# TSAL_logic.net
KiCad netlist of a schematic drawn in EAGLE
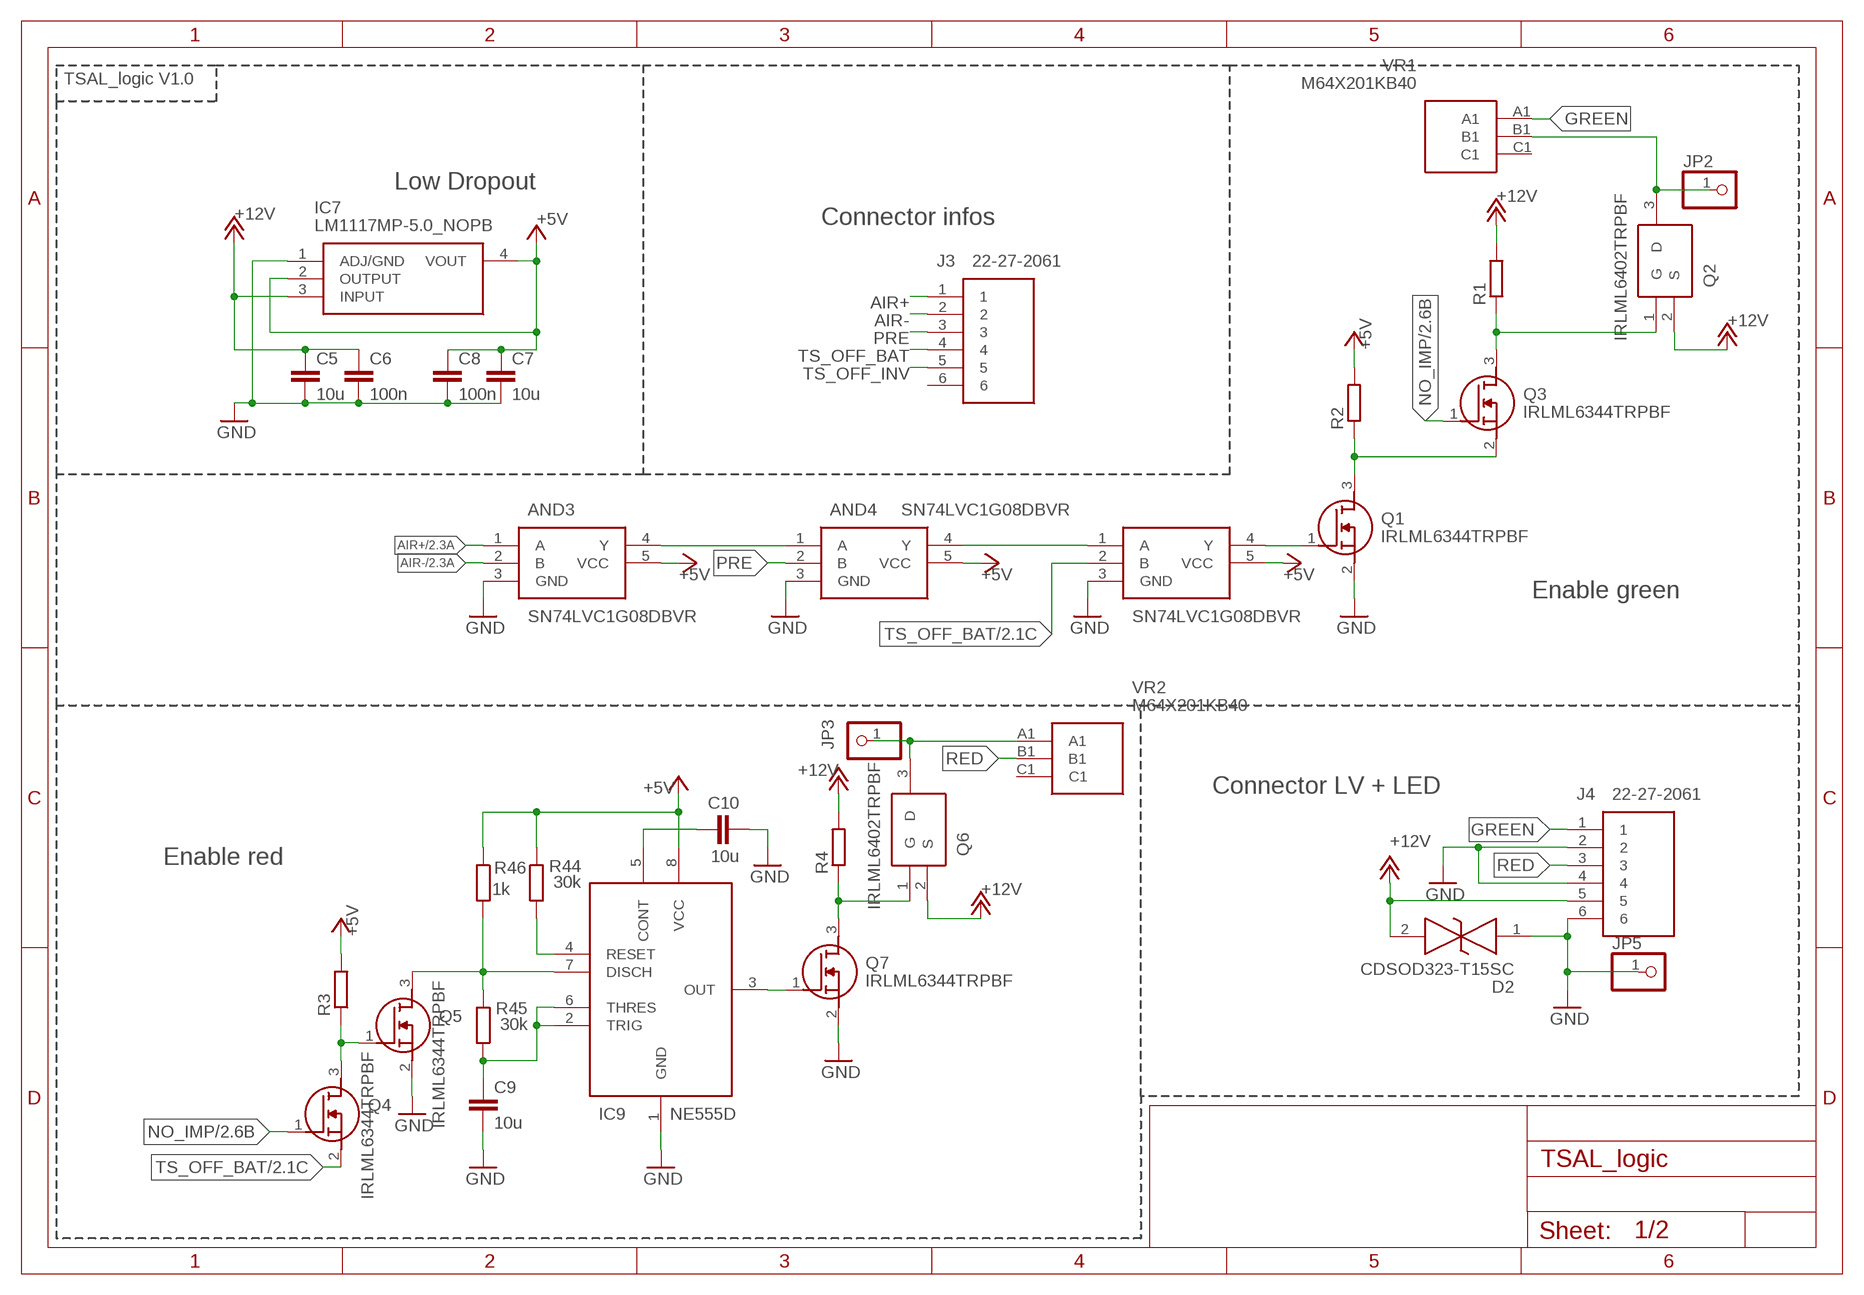
[diagram p0: schematic, sheet 1]
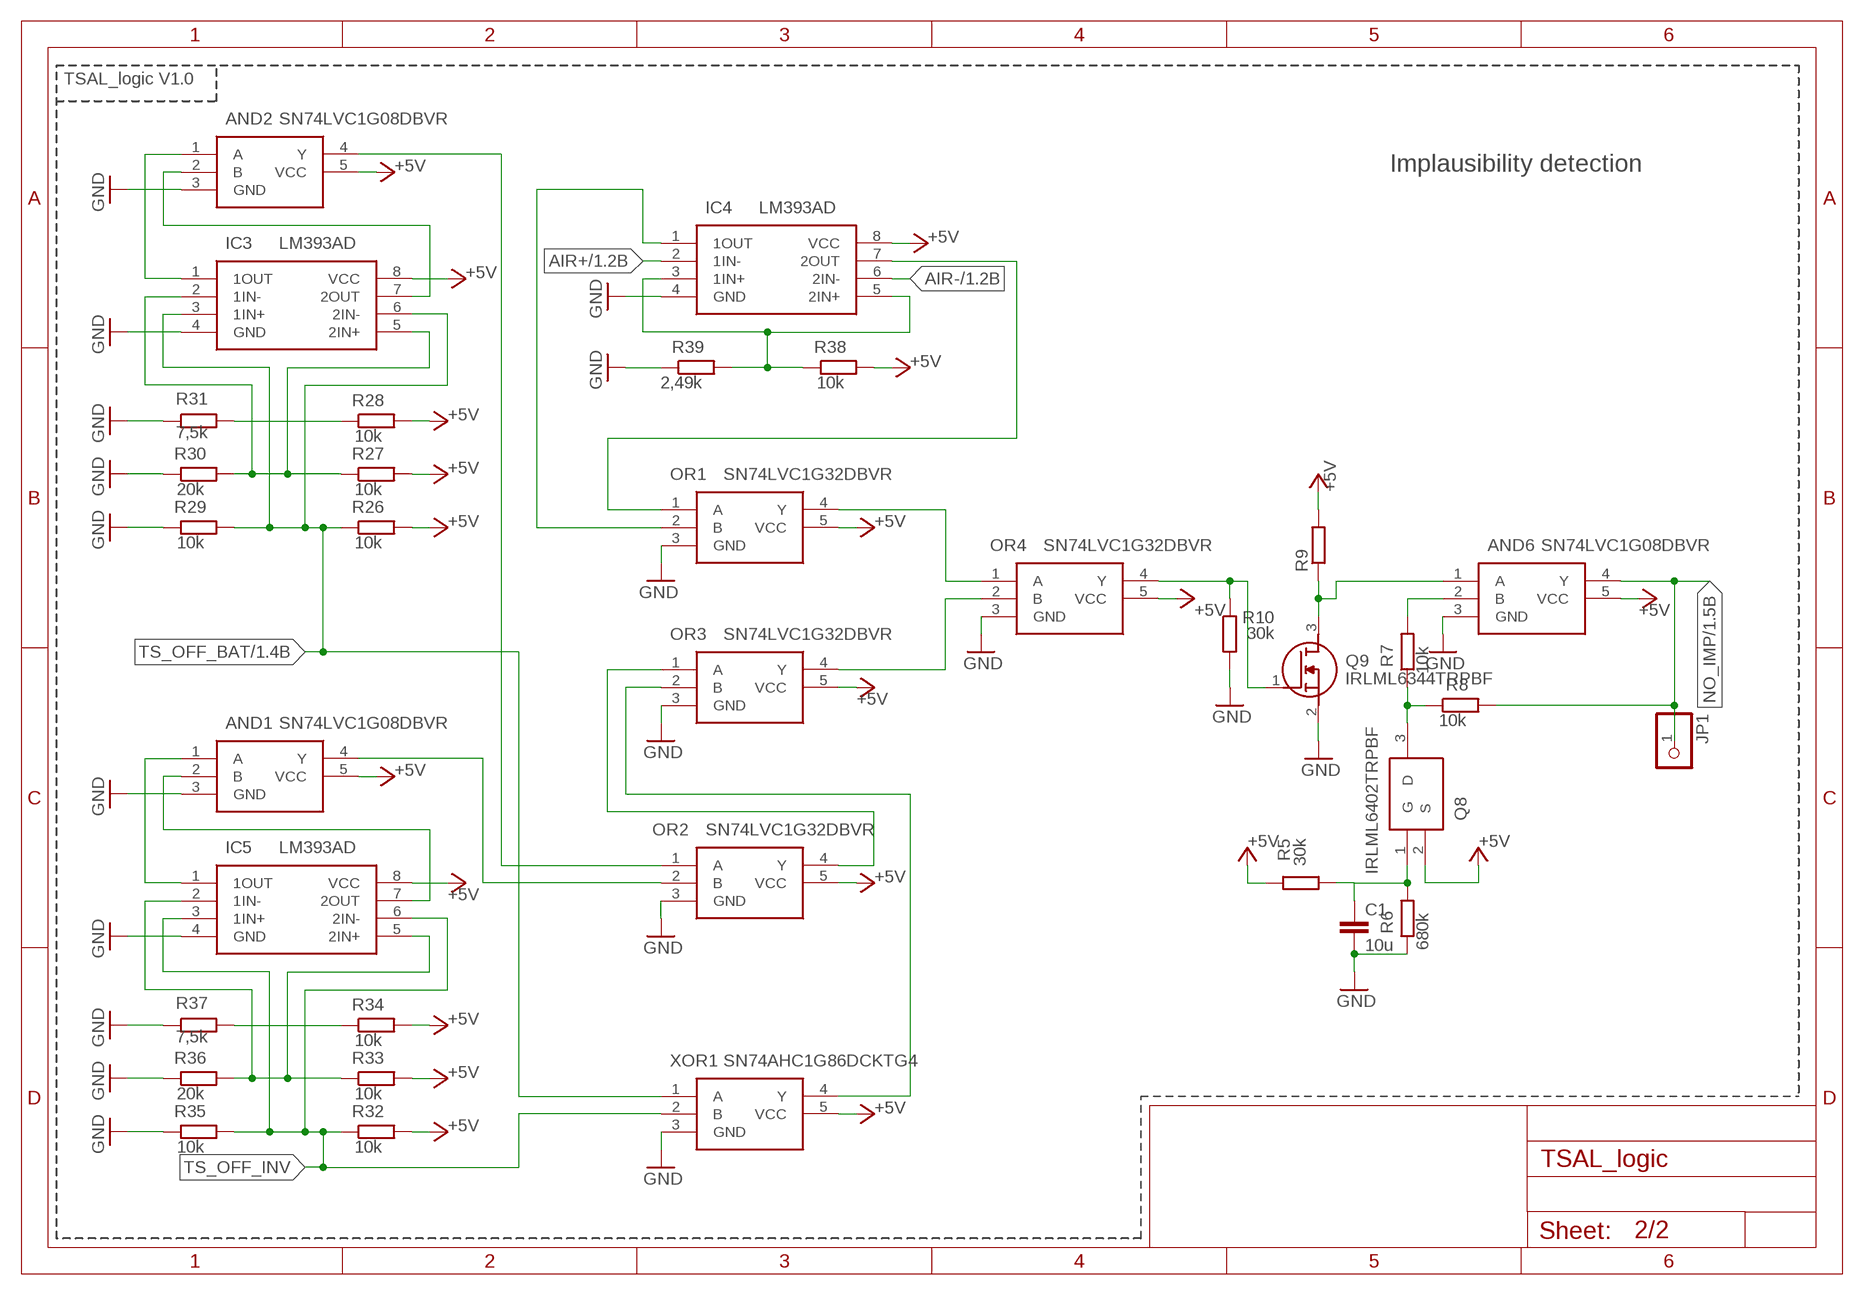
[diagram p1: schematic, sheet 2]

(export (version "E")
  (design (tool "Eeschema 10.0.6"))
  (components
    (comp (ref "AND1")
      (value "SN74LVC1G08DBVR")
      (footprint "eagle-import:SOT95P280X145-5N")
      (fields (field (name "MOUSER_PART_NUMBER") "595-SN74LVC1G08DBVR"))
      (libsource (lib "eagle-import") (part "SN74LVC1G08DBVR"))
    )
    (comp (ref "AND2")
      (value "SN74LVC1G08DBVR")
      (footprint "eagle-import:SOT95P280X145-5N")
      (fields (field (name "MOUSER_PART_NUMBER") "595-SN74LVC1G08DBVR"))
      (libsource (lib "eagle-import") (part "SN74LVC1G08DBVR"))
    )
    (comp (ref "AND6")
      (value "SN74LVC1G08DBVR")
      (footprint "eagle-import:SOT95P280X145-5N")
      (fields (field (name "MOUSER_PART_NUMBER") "595-SN74LVC1G08DBVR"))
      (libsource (lib "eagle-import") (part "SN74LVC1G08DBVR"))
    )
    (comp (ref "C1")
      (value "10u")
      (footprint "eagle-import:C1206")
      (libsource (lib "eagle-import") (part "C-EUC1206"))
    )
    (comp (ref "IC3")
      (value "LM393AD")
      (footprint "eagle-import:SOIC127P600X175-8N")
      (fields (field (name "RS_PART_NUMBER") "5171905P"))
      (libsource (lib "eagle-import") (part "LM393AD"))
    )
    (comp (ref "IC4")
      (value "LM393AD")
      (footprint "eagle-import:SOIC127P600X175-8N")
      (fields (field (name "RS_PART_NUMBER") "5171905P"))
      (libsource (lib "eagle-import") (part "LM393AD"))
    )
    (comp (ref "IC5")
      (value "LM393AD")
      (footprint "eagle-import:SOIC127P600X175-8N")
      (fields (field (name "RS_PART_NUMBER") "5171905P"))
      (libsource (lib "eagle-import") (part "LM393AD"))
    )
    (comp (ref "JP1")
      (value "PINHD-1X1")
      (footprint "eagle-import:1X01")
      (libsource (lib "eagle-import") (part "PINHD-1X1"))
    )
    (comp (ref "OR1")
      (value "SN74LVC1G32DBVR")
      (footprint "eagle-import:SOT95P280X145-5N")
      (fields (field (name "RS_PART_NUMBER") "0527669"))
      (libsource (lib "eagle-import") (part "SN74LVC1G32DBVR"))
    )
    (comp (ref "OR2")
      (value "SN74LVC1G32DBVR")
      (footprint "eagle-import:SOT95P280X145-5N")
      (fields (field (name "RS_PART_NUMBER") "0527669"))
      (libsource (lib "eagle-import") (part "SN74LVC1G32DBVR"))
    )
    (comp (ref "OR3")
      (value "SN74LVC1G32DBVR")
      (footprint "eagle-import:SOT95P280X145-5N")
      (fields (field (name "RS_PART_NUMBER") "0527669") (field (name "SPICEPREFIX") "X"))
      (libsource (lib "eagle-import") (part "SN74LVC1G32DBVR"))
    )
    (comp (ref "OR4")
      (value "SN74LVC1G32DBVR")
      (footprint "eagle-import:SOT95P280X145-5N")
      (fields (field (name "RS_PART_NUMBER") "0527669"))
      (libsource (lib "eagle-import") (part "SN74LVC1G32DBVR"))
    )
    (comp (ref "Q8")
      (value "IRLML6402TRPBF")
      (footprint "eagle-import:SOT95P237X112-3N")
      (fields (field (name "RS_PART_NUMBER") "0301322P"))
      (libsource (lib "eagle-import") (part "IRLML6402TRPBF"))
    )
    (comp (ref "Q9")
      (value "IRLML6344TRPBF")
      (footprint "eagle-import:SOT95P237X112-3N")
      (fields (field (name "RS_PART_NUMBER") "7377225P"))
      (libsource (lib "eagle-import") (part "IRLML6344TRPBF"))
    )
    (comp (ref "R5")
      (value "30k")
      (footprint "eagle-import:R1206")
      (libsource (lib "eagle-import") (part "R-EU_R1206"))
    )
    (comp (ref "R6")
      (value "680k")
      (footprint "eagle-import:R0603")
      (libsource (lib "eagle-import") (part "R-EU_R0603"))
    )
    (comp (ref "R7")
      (value "10k")
      (footprint "eagle-import:R0603")
      (libsource (lib "eagle-import") (part "R-EU_R0603"))
    )
    (comp (ref "R8")
      (value "10k")
      (footprint "eagle-import:R0603")
      (libsource (lib "eagle-import") (part "R-EU_R0603"))
    )
    (comp (ref "R9")
      (value "R-EU_R0603")
      (footprint "eagle-import:R0603")
      (libsource (lib "eagle-import") (part "R-EU_R0603"))
    )
    (comp (ref "R10")
      (value "30k")
      (footprint "eagle-import:R1206")
      (libsource (lib "eagle-import") (part "R-EU_R1206"))
    )
    (comp (ref "R26")
      (value "10k")
      (footprint "eagle-import:R0603")
      (libsource (lib "eagle-import") (part "R-EU_R0603"))
    )
    (comp (ref "R27")
      (value "10k")
      (footprint "eagle-import:R0603")
      (libsource (lib "eagle-import") (part "R-EU_R0603"))
    )
    (comp (ref "R28")
      (value "10k")
      (footprint "eagle-import:R0603")
      (libsource (lib "eagle-import") (part "R-EU_R0603"))
    )
    (comp (ref "R29")
      (value "10k")
      (footprint "eagle-import:R0603")
      (libsource (lib "eagle-import") (part "R-EU_R0603"))
    )
    (comp (ref "R30")
      (value "20k")
      (footprint "eagle-import:R0603")
      (libsource (lib "eagle-import") (part "R-EU_R0603"))
    )
    (comp (ref "R31")
      (value "7,5k")
      (footprint "eagle-import:R0805")
      (libsource (lib "eagle-import") (part "R-EU_R0805"))
    )
    (comp (ref "R32")
      (value "10k")
      (footprint "eagle-import:R0603")
      (libsource (lib "eagle-import") (part "R-EU_R0603"))
    )
    (comp (ref "R33")
      (value "10k")
      (footprint "eagle-import:R0603")
      (libsource (lib "eagle-import") (part "R-EU_R0603"))
    )
    (comp (ref "R34")
      (value "10k")
      (footprint "eagle-import:R0603")
      (libsource (lib "eagle-import") (part "R-EU_R0603"))
    )
    (comp (ref "R35")
      (value "10k")
      (footprint "eagle-import:R0603")
      (libsource (lib "eagle-import") (part "R-EU_R0603"))
    )
    (comp (ref "R36")
      (value "20k")
      (footprint "eagle-import:R0603")
      (libsource (lib "eagle-import") (part "R-EU_R0603"))
    )
    (comp (ref "R37")
      (value "7,5k")
      (footprint "eagle-import:R0805")
      (libsource (lib "eagle-import") (part "R-EU_R0805"))
    )
    (comp (ref "R38")
      (value "10k")
      (footprint "eagle-import:R0603")
      (libsource (lib "eagle-import") (part "R-EU_R0603"))
    )
    (comp (ref "R39")
      (value "2,49k")
      (footprint "eagle-import:R0603")
      (libsource (lib "eagle-import") (part "R-EU_R0603"))
    )
    (comp (ref "XOR1")
      (value "SN74AHC1G86DCKTG4")
      (footprint "eagle-import:SOT65P210X110-5N")
      (fields (field (name "MOUSER_PART_NUMBER") "595-74AHC1G86DCKTG4"))
      (libsource (lib "eagle-import") (part "SN74AHC1G86DCKTG4"))
    )
    (comp (ref "AND3")
      (value "SN74LVC1G08DBVR")
      (footprint "eagle-import:SOT95P280X145-5N")
      (fields (field (name "MOUSER_PART_NUMBER") "595-SN74LVC1G08DBVR"))
      (libsource (lib "eagle-import") (part "SN74LVC1G08DBVR"))
    )
    (comp (ref "AND4")
      (value "SN74LVC1G08DBVR")
      (footprint "eagle-import:SOT95P280X145-5N")
      (fields (field (name "MOUSER_PART_NUMBER") "595-SN74LVC1G08DBVR"))
      (libsource (lib "eagle-import") (part "SN74LVC1G08DBVR"))
    )
    (comp (ref "AND5")
      (value "SN74LVC1G08DBVR")
      (footprint "eagle-import:SOT95P280X145-5N")
      (fields (field (name "MOUSER_PART_NUMBER") "595-SN74LVC1G08DBVR"))
      (libsource (lib "eagle-import") (part "SN74LVC1G08DBVR"))
    )
    (comp (ref "C5")
      (value "10u")
      (footprint "eagle-import:C1206")
      (libsource (lib "eagle-import") (part "C-EUC1206"))
    )
    (comp (ref "C6")
      (value "100n")
      (footprint "eagle-import:C0603")
      (libsource (lib "eagle-import") (part "C-EUC0603"))
    )
    (comp (ref "C7")
      (value "10u")
      (footprint "eagle-import:C1206")
      (libsource (lib "eagle-import") (part "C-EUC1206"))
    )
    (comp (ref "C8")
      (value "100n")
      (footprint "eagle-import:C0603")
      (libsource (lib "eagle-import") (part "C-EUC0603"))
    )
    (comp (ref "C9")
      (value "10u")
      (footprint "eagle-import:C1206")
      (libsource (lib "eagle-import") (part "C-EUC1206"))
    )
    (comp (ref "C10")
      (value "10u")
      (footprint "eagle-import:C1206")
      (libsource (lib "eagle-import") (part "C-EUC1206"))
    )
    (comp (ref "D2")
      (value "CDSOD323-T15SC")
      (footprint "eagle-import:SOD-323")
      (fields (field (name "RS_PART_NUMBER") "7734570"))
      (libsource (lib "eagle-import") (part "CDSOD323-T15SC"))
    )
    (comp (ref "IC7")
      (value "LM1117MP-5.0_NOPB")
      (footprint "eagle-import:SOT230P700X180-4N")
      (fields
        (field (name "ARROW_PART_NUMBER") "LM1117MP-5.0/NOPB")
        (field (name "MOUSER_PART_NUMBER") "926-LM1117MP-5.0NOPB")
      )
      (libsource (lib "eagle-import") (part "LM1117MP-5.0_NOPB"))
    )
    (comp (ref "IC9")
      (value "NE555D")
      (footprint "eagle-import:SOIC127P600X175-8N")
      (fields (field (name "RS_PART_NUMBER") "6624661P"))
      (libsource (lib "eagle-import") (part "NE555D"))
    )
    (comp (ref "J3")
      (value "22-27-2061")
      (footprint "eagle-import:HDRV6W64P0X254_1X6_1524X580X11")
      (fields (field (name "RS_PART_NUMBER") "4838506P"))
      (libsource (lib "eagle-import") (part "22-27-2061"))
    )
    (comp (ref "J4")
      (value "22-27-2061")
      (footprint "eagle-import:HDRV6W64P0X254_1X6_1524X580X11")
      (fields (field (name "RS_PART_NUMBER") "4838506P"))
      (libsource (lib "eagle-import") (part "22-27-2061"))
    )
    (comp (ref "JP2")
      (value "PINHD-1X1")
      (footprint "eagle-import:1X01")
      (libsource (lib "eagle-import") (part "PINHD-1X1"))
    )
    (comp (ref "JP3")
      (value "PINHD-1X1")
      (footprint "eagle-import:1X01")
      (libsource (lib "eagle-import") (part "PINHD-1X1"))
    )
    (comp (ref "JP5")
      (value "PINHD-1X1")
      (footprint "eagle-import:1X01")
      (libsource (lib "eagle-import") (part "PINHD-1X1"))
    )
    (comp (ref "Q1")
      (value "IRLML6344TRPBF")
      (footprint "eagle-import:SOT95P237X112-3N")
      (fields (field (name "RS_PART_NUMBER") "7377225P"))
      (libsource (lib "eagle-import") (part "IRLML6344TRPBF"))
    )
    (comp (ref "Q2")
      (value "IRLML6402TRPBF")
      (footprint "eagle-import:SOT95P237X112-3N")
      (fields (field (name "RS_PART_NUMBER") "0301322P"))
      (libsource (lib "eagle-import") (part "IRLML6402TRPBF"))
    )
    (comp (ref "Q3")
      (value "IRLML6344TRPBF")
      (footprint "eagle-import:SOT95P237X112-3N")
      (fields (field (name "RS_PART_NUMBER") "7377225P"))
      (libsource (lib "eagle-import") (part "IRLML6344TRPBF"))
    )
    (comp (ref "Q4")
      (value "IRLML6344TRPBF")
      (footprint "eagle-import:SOT95P237X112-3N")
      (fields (field (name "RS_PART_NUMBER") "7377225P"))
      (libsource (lib "eagle-import") (part "IRLML6344TRPBF"))
    )
    (comp (ref "Q5")
      (value "IRLML6344TRPBF")
      (footprint "eagle-import:SOT95P237X112-3N")
      (fields (field (name "RS_PART_NUMBER") "7377225P"))
      (libsource (lib "eagle-import") (part "IRLML6344TRPBF"))
    )
    (comp (ref "Q6")
      (value "IRLML6402TRPBF")
      (footprint "eagle-import:SOT95P237X112-3N")
      (fields (field (name "RS_PART_NUMBER") "0301322P"))
      (libsource (lib "eagle-import") (part "IRLML6402TRPBF"))
    )
    (comp (ref "Q7")
      (value "IRLML6344TRPBF")
      (footprint "eagle-import:SOT95P237X112-3N")
      (fields (field (name "RS_PART_NUMBER") "7377225P"))
      (libsource (lib "eagle-import") (part "IRLML6344TRPBF"))
    )
    (comp (ref "R1")
      (value "R-EU_R0603")
      (footprint "eagle-import:R0603")
      (libsource (lib "eagle-import") (part "R-EU_R0603"))
    )
    (comp (ref "R2")
      (value "R-EU_R0603")
      (footprint "eagle-import:R0603")
      (libsource (lib "eagle-import") (part "R-EU_R0603"))
    )
    (comp (ref "R3")
      (value "R-EU_R0603")
      (footprint "eagle-import:R0603")
      (libsource (lib "eagle-import") (part "R-EU_R0603"))
    )
    (comp (ref "R4")
      (value "R-EU_R0603")
      (footprint "eagle-import:R0603")
      (libsource (lib "eagle-import") (part "R-EU_R0603"))
    )
    (comp (ref "R44")
      (value "30k")
      (footprint "eagle-import:R1206")
      (libsource (lib "eagle-import") (part "R-EU_R1206"))
    )
    (comp (ref "R45")
      (value "30k")
      (footprint "eagle-import:R1206")
      (libsource (lib "eagle-import") (part "R-EU_R1206"))
    )
    (comp (ref "R46")
      (value "1k")
      (footprint "eagle-import:R1206")
      (libsource (lib "eagle-import") (part "R-EU_R1206"))
    )
    (comp (ref "VR1")
      (value "M64X201KB40")
      (footprint "eagle-import:M64X201KB40")
      (fields (field (name "MOUSER_PART_NUMBER") "594-64X201"))
      (libsource (lib "eagle-import") (part "M64X201KB40"))
    )
    (comp (ref "VR2")
      (value "M64X201KB40")
      (footprint "eagle-import:M64X201KB40")
      (fields (field (name "MOUSER_PART_NUMBER") "594-64X201"))
      (libsource (lib "eagle-import") (part "M64X201KB40"))
    )
  )
  (nets
    (net (code "1") (name "+5V") (class "Default")
      (node (ref "AND1") (pin "5") (pinfunction "VCC_5") (pintype "power_in"))
      (node (ref "AND2") (pin "5") (pinfunction "VCC_5") (pintype "power_in"))
      (node (ref "AND3") (pin "5") (pinfunction "VCC_5") (pintype "power_in"))
      (node (ref "AND4") (pin "5") (pinfunction "VCC_5") (pintype "power_in"))
      (node (ref "AND5") (pin "5") (pinfunction "VCC_5") (pintype "power_in"))
      (node (ref "AND6") (pin "5") (pinfunction "VCC_5") (pintype "power_in"))
      (node (ref "C7") (pin "1") (pinfunction "1_1") (pintype "passive"))
      (node (ref "C8") (pin "1") (pinfunction "1_1") (pintype "passive"))
      (node (ref "IC3") (pin "8") (pinfunction "VCC_8") (pintype "bidirectional"))
      (node (ref "IC4") (pin "8") (pinfunction "VCC_8") (pintype "bidirectional"))
      (node (ref "IC5") (pin "8") (pinfunction "VCC_8") (pintype "bidirectional"))
      (node (ref "IC7") (pin "2") (pinfunction "OUTPUT_2") (pintype "bidirectional"))
      (node (ref "IC7") (pin "4") (pinfunction "VOUT_4") (pintype "bidirectional"))
      (node (ref "IC9") (pin "8") (pinfunction "VCC_8") (pintype "bidirectional"))
      (node (ref "OR1") (pin "5") (pinfunction "VCC_5") (pintype "bidirectional"))
      (node (ref "OR2") (pin "5") (pinfunction "VCC_5") (pintype "bidirectional"))
      (node (ref "OR3") (pin "5") (pinfunction "VCC_5") (pintype "bidirectional"))
      (node (ref "OR4") (pin "5") (pinfunction "VCC_5") (pintype "bidirectional"))
      (node (ref "Q8") (pin "2") (pinfunction "S_2") (pintype "bidirectional"))
      (node (ref "R2") (pin "2") (pinfunction "2_2") (pintype "passive"))
      (node (ref "R26") (pin "2") (pinfunction "2_2") (pintype "passive"))
      (node (ref "R27") (pin "2") (pinfunction "2_2") (pintype "passive"))
      (node (ref "R28") (pin "2") (pinfunction "2_2") (pintype "passive"))
      (node (ref "R3") (pin "2") (pinfunction "2_2") (pintype "passive"))
      (node (ref "R32") (pin "2") (pinfunction "2_2") (pintype "passive"))
      (node (ref "R33") (pin "2") (pinfunction "2_2") (pintype "passive"))
      (node (ref "R34") (pin "2") (pinfunction "2_2") (pintype "passive"))
      (node (ref "R38") (pin "2") (pinfunction "2_2") (pintype "passive"))
      (node (ref "R44") (pin "1") (pinfunction "1_1") (pintype "passive"))
      (node (ref "R46") (pin "1") (pinfunction "1_1") (pintype "passive"))
      (node (ref "R5") (pin "1") (pinfunction "1_1") (pintype "passive"))
      (node (ref "R9") (pin "2") (pinfunction "2_2") (pintype "passive"))
      (node (ref "XOR1") (pin "5") (pinfunction "VCC_5") (pintype "bidirectional"))
    )
    (net (code "2") (name "+12V") (class "Default")
      (node (ref "C5") (pin "1") (pinfunction "1_1") (pintype "passive"))
      (node (ref "C6") (pin "1") (pinfunction "1_1") (pintype "passive"))
      (node (ref "D2") (pin "2") (pinfunction "2_2") (pintype "bidirectional"))
      (node (ref "IC7") (pin "3") (pinfunction "INPUT_3") (pintype "bidirectional"))
      (node (ref "J4") (pin "5") (pinfunction "5_5") (pintype "bidirectional"))
      (node (ref "Q2") (pin "2") (pinfunction "S_2") (pintype "bidirectional"))
      (node (ref "Q6") (pin "2") (pinfunction "S_2") (pintype "bidirectional"))
      (node (ref "R1") (pin "2") (pinfunction "2_2") (pintype "passive"))
      (node (ref "R4") (pin "2") (pinfunction "2_2") (pintype "passive"))
    )
    (net (code "3") (name "AIR+") (class "Default")
      (node (ref "AND3") (pin "1") (pinfunction "A_1") (pintype "input"))
      (node (ref "IC4") (pin "2") (pinfunction "1IN-_2") (pintype "bidirectional"))
      (node (ref "J3") (pin "1") (pinfunction "1_1") (pintype "bidirectional"))
    )
    (net (code "4") (name "AIR-") (class "Default")
      (node (ref "AND3") (pin "2") (pinfunction "B_2") (pintype "input"))
      (node (ref "IC4") (pin "6") (pinfunction "2IN-_6") (pintype "bidirectional"))
      (node (ref "J3") (pin "2") (pinfunction "2_2") (pintype "bidirectional"))
    )
    (net (code "5") (name "GND") (class "Default")
      (node (ref "AND1") (pin "3") (pinfunction "GND_3") (pintype "power_in"))
      (node (ref "AND2") (pin "3") (pinfunction "GND_3") (pintype "power_in"))
      (node (ref "AND3") (pin "3") (pinfunction "GND_3") (pintype "power_in"))
      (node (ref "AND4") (pin "3") (pinfunction "GND_3") (pintype "power_in"))
      (node (ref "AND5") (pin "3") (pinfunction "GND_3") (pintype "power_in"))
      (node (ref "AND6") (pin "3") (pinfunction "GND_3") (pintype "power_in"))
      (node (ref "C1") (pin "2") (pinfunction "2_2") (pintype "passive"))
      (node (ref "C10") (pin "2") (pinfunction "2_2") (pintype "passive"))
      (node (ref "C5") (pin "2") (pinfunction "2_2") (pintype "passive"))
      (node (ref "C6") (pin "2") (pinfunction "2_2") (pintype "passive"))
      (node (ref "C7") (pin "2") (pinfunction "2_2") (pintype "passive"))
      (node (ref "C8") (pin "2") (pinfunction "2_2") (pintype "passive"))
      (node (ref "C9") (pin "2") (pinfunction "2_2") (pintype "passive"))
      (node (ref "D2") (pin "1") (pinfunction "1_1") (pintype "bidirectional"))
      (node (ref "IC3") (pin "4") (pinfunction "GND_4") (pintype "bidirectional"))
      (node (ref "IC4") (pin "4") (pinfunction "GND_4") (pintype "bidirectional"))
      (node (ref "IC5") (pin "4") (pinfunction "GND_4") (pintype "bidirectional"))
      (node (ref "IC7") (pin "1") (pinfunction "ADJ/GND_1") (pintype "bidirectional"))
      (node (ref "IC9") (pin "1") (pinfunction "GND_1") (pintype "bidirectional"))
      (node (ref "J4") (pin "2") (pinfunction "2_2") (pintype "bidirectional"))
      (node (ref "J4") (pin "4") (pinfunction "4_4") (pintype "bidirectional"))
      (node (ref "J4") (pin "6") (pinfunction "6_6") (pintype "bidirectional"))
      (node (ref "JP5") (pin "1") (pinfunction "1_1") (pintype "passive"))
      (node (ref "OR1") (pin "3") (pinfunction "GND_3") (pintype "bidirectional"))
      (node (ref "OR2") (pin "3") (pinfunction "GND_3") (pintype "bidirectional"))
      (node (ref "OR3") (pin "3") (pinfunction "GND_3") (pintype "bidirectional"))
      (node (ref "OR4") (pin "3") (pinfunction "GND_3") (pintype "bidirectional"))
      (node (ref "Q1") (pin "2") (pinfunction "S_2") (pintype "bidirectional"))
      (node (ref "Q5") (pin "2") (pinfunction "S_2") (pintype "bidirectional"))
      (node (ref "Q7") (pin "2") (pinfunction "S_2") (pintype "bidirectional"))
      (node (ref "Q9") (pin "2") (pinfunction "S_2") (pintype "bidirectional"))
      (node (ref "R10") (pin "2") (pinfunction "2_2") (pintype "passive"))
      (node (ref "R29") (pin "1") (pinfunction "1_1") (pintype "passive"))
      (node (ref "R30") (pin "1") (pinfunction "1_1") (pintype "passive"))
      (node (ref "R31") (pin "1") (pinfunction "1_1") (pintype "passive"))
      (node (ref "R35") (pin "1") (pinfunction "1_1") (pintype "passive"))
      (node (ref "R36") (pin "1") (pinfunction "1_1") (pintype "passive"))
      (node (ref "R37") (pin "1") (pinfunction "1_1") (pintype "passive"))
      (node (ref "R39") (pin "1") (pinfunction "1_1") (pintype "passive"))
      (node (ref "R6") (pin "1") (pinfunction "1_1") (pintype "passive"))
      (node (ref "XOR1") (pin "3") (pinfunction "GND_3") (pintype "bidirectional"))
    )
    (net (code "6") (name "GREEN") (class "Default")
      (node (ref "J4") (pin "1") (pinfunction "1_1") (pintype "bidirectional"))
      (node (ref "VR1") (pin "A1") (pinfunction "A1_A1") (pintype "bidirectional"))
    )
    (net (code "7") (name "NO_IMP") (class "Default")
      (node (ref "AND6") (pin "4") (pinfunction "Y_4") (pintype "output"))
      (node (ref "JP1") (pin "1") (pinfunction "1_1") (pintype "passive"))
      (node (ref "Q3") (pin "1") (pinfunction "G_1") (pintype "bidirectional"))
      (node (ref "Q4") (pin "1") (pinfunction "G_1") (pintype "bidirectional"))
      (node (ref "R8") (pin "2") (pinfunction "2_2") (pintype "passive"))
    )
    (net (code "8") (name "Net-(AND1-A)") (class "Default")
      (node (ref "AND1") (pin "1") (pinfunction "A_1") (pintype "input"))
      (node (ref "IC5") (pin "1") (pinfunction "1OUT_1") (pintype "bidirectional"))
    )
    (net (code "9") (name "Net-(AND1-B)") (class "Default")
      (node (ref "AND1") (pin "2") (pinfunction "B_2") (pintype "input"))
      (node (ref "IC5") (pin "7") (pinfunction "2OUT_7") (pintype "bidirectional"))
    )
    (net (code "10") (name "Net-(AND1-Y)") (class "Default")
      (node (ref "AND1") (pin "4") (pinfunction "Y_4") (pintype "output"))
      (node (ref "OR2") (pin "2") (pinfunction "B_2") (pintype "bidirectional"))
    )
    (net (code "11") (name "Net-(AND2-A)") (class "Default")
      (node (ref "AND2") (pin "1") (pinfunction "A_1") (pintype "input"))
      (node (ref "IC3") (pin "1") (pinfunction "1OUT_1") (pintype "bidirectional"))
    )
    (net (code "12") (name "Net-(AND2-B)") (class "Default")
      (node (ref "AND2") (pin "2") (pinfunction "B_2") (pintype "input"))
      (node (ref "IC3") (pin "7") (pinfunction "2OUT_7") (pintype "bidirectional"))
    )
    (net (code "13") (name "Net-(AND2-Y)") (class "Default")
      (node (ref "AND2") (pin "4") (pinfunction "Y_4") (pintype "output"))
      (node (ref "OR2") (pin "1") (pinfunction "A_1") (pintype "bidirectional"))
    )
    (net (code "14") (name "Net-(AND3-Y)") (class "Default")
      (node (ref "AND3") (pin "4") (pinfunction "Y_4") (pintype "output"))
      (node (ref "AND4") (pin "1") (pinfunction "A_1") (pintype "input"))
    )
    (net (code "15") (name "Net-(AND4-Y)") (class "Default")
      (node (ref "AND4") (pin "4") (pinfunction "Y_4") (pintype "output"))
      (node (ref "AND5") (pin "1") (pinfunction "A_1") (pintype "input"))
    )
    (net (code "16") (name "Net-(AND5-Y)") (class "Default")
      (node (ref "AND5") (pin "4") (pinfunction "Y_4") (pintype "output"))
      (node (ref "Q1") (pin "1") (pinfunction "G_1") (pintype "bidirectional"))
    )
    (net (code "17") (name "Net-(AND6-A)") (class "Default")
      (node (ref "AND6") (pin "1") (pinfunction "A_1") (pintype "input"))
      (node (ref "Q9") (pin "3") (pinfunction "D_3") (pintype "bidirectional"))
      (node (ref "R9") (pin "1") (pinfunction "1_1") (pintype "passive"))
    )
    (net (code "18") (name "Net-(AND6-B)") (class "Default")
      (node (ref "AND6") (pin "2") (pinfunction "B_2") (pintype "input"))
      (node (ref "R7") (pin "2") (pinfunction "2_2") (pintype "passive"))
    )
    (net (code "19") (name "Net-(IC3-1IN-)") (class "Default")
      (node (ref "IC3") (pin "2") (pinfunction "1IN-_2") (pintype "bidirectional"))
      (node (ref "IC3") (pin "5") (pinfunction "2IN+_5") (pintype "bidirectional"))
      (node (ref "R27") (pin "1") (pinfunction "1_1") (pintype "passive"))
      (node (ref "R30") (pin "2") (pinfunction "2_2") (pintype "passive"))
    )
    (net (code "20") (name "Net-(IC4-1IN+)") (class "Default")
      (node (ref "IC4") (pin "3") (pinfunction "1IN+_3") (pintype "bidirectional"))
      (node (ref "IC4") (pin "5") (pinfunction "2IN+_5") (pintype "bidirectional"))
      (node (ref "R38") (pin "1") (pinfunction "1_1") (pintype "passive"))
      (node (ref "R39") (pin "2") (pinfunction "2_2") (pintype "passive"))
    )
    (net (code "21") (name "Net-(IC4-1OUT)") (class "Default")
      (node (ref "IC4") (pin "1") (pinfunction "1OUT_1") (pintype "bidirectional"))
      (node (ref "OR1") (pin "2") (pinfunction "B_2") (pintype "bidirectional"))
    )
    (net (code "22") (name "Net-(IC4-2OUT)") (class "Default")
      (node (ref "IC4") (pin "7") (pinfunction "2OUT_7") (pintype "bidirectional"))
      (node (ref "OR1") (pin "1") (pinfunction "A_1") (pintype "bidirectional"))
    )
    (net (code "23") (name "Net-(IC5-1IN-)") (class "Default")
      (node (ref "IC5") (pin "2") (pinfunction "1IN-_2") (pintype "bidirectional"))
      (node (ref "IC5") (pin "5") (pinfunction "2IN+_5") (pintype "bidirectional"))
      (node (ref "R33") (pin "1") (pinfunction "1_1") (pintype "passive"))
      (node (ref "R36") (pin "2") (pinfunction "2_2") (pintype "passive"))
    )
    (net (code "24") (name "Net-(IC9-CONT)") (class "Default")
      (node (ref "C10") (pin "1") (pinfunction "1_1") (pintype "passive"))
      (node (ref "IC9") (pin "5") (pinfunction "CONT_5") (pintype "bidirectional"))
    )
    (net (code "25") (name "Net-(IC9-DISCH)") (class "Default")
      (node (ref "IC9") (pin "7") (pinfunction "DISCH_7") (pintype "bidirectional"))
      (node (ref "Q5") (pin "3") (pinfunction "D_3") (pintype "bidirectional"))
      (node (ref "R45") (pin "2") (pinfunction "2_2") (pintype "passive"))
      (node (ref "R46") (pin "2") (pinfunction "2_2") (pintype "passive"))
    )
    (net (code "26") (name "Net-(IC9-OUT)") (class "Default")
      (node (ref "IC9") (pin "3") (pinfunction "OUT_3") (pintype "bidirectional"))
      (node (ref "Q7") (pin "1") (pinfunction "G_1") (pintype "bidirectional"))
    )
    (net (code "27") (name "Net-(IC9-RESET)") (class "Default")
      (node (ref "IC9") (pin "4") (pinfunction "RESET_4") (pintype "bidirectional"))
      (node (ref "R44") (pin "2") (pinfunction "2_2") (pintype "passive"))
    )
    (net (code "28") (name "Net-(IC9-THRES)") (class "Default")
      (node (ref "C9") (pin "1") (pinfunction "1_1") (pintype "passive"))
      (node (ref "IC9") (pin "2") (pinfunction "TRIG_2") (pintype "bidirectional"))
      (node (ref "IC9") (pin "6") (pinfunction "THRES_6") (pintype "bidirectional"))
      (node (ref "R45") (pin "1") (pinfunction "1_1") (pintype "passive"))
    )
    (net (code "29") (name "Net-(OR1-Y)") (class "Default")
      (node (ref "OR1") (pin "4") (pinfunction "Y_4") (pintype "bidirectional"))
      (node (ref "OR4") (pin "1") (pinfunction "A_1") (pintype "bidirectional"))
    )
    (net (code "30") (name "Net-(OR2-Y)") (class "Default")
      (node (ref "OR2") (pin "4") (pinfunction "Y_4") (pintype "bidirectional"))
      (node (ref "OR3") (pin "1") (pinfunction "A_1") (pintype "bidirectional"))
    )
    (net (code "31") (name "Net-(OR3-B)") (class "Default")
      (node (ref "OR3") (pin "2") (pinfunction "B_2") (pintype "bidirectional"))
      (node (ref "XOR1") (pin "4") (pinfunction "Y_4") (pintype "bidirectional"))
    )
    (net (code "32") (name "Net-(OR3-Y)") (class "Default")
      (node (ref "OR3") (pin "4") (pinfunction "Y_4") (pintype "bidirectional"))
      (node (ref "OR4") (pin "2") (pinfunction "B_2") (pintype "bidirectional"))
    )
    (net (code "33") (name "Net-(OR4-Y)") (class "Default")
      (node (ref "OR4") (pin "4") (pinfunction "Y_4") (pintype "bidirectional"))
      (node (ref "Q9") (pin "1") (pinfunction "G_1") (pintype "bidirectional"))
      (node (ref "R10") (pin "1") (pinfunction "1_1") (pintype "passive"))
    )
    (net (code "34") (name "Net-(Q1-D)") (class "Default")
      (node (ref "Q1") (pin "3") (pinfunction "D_3") (pintype "bidirectional"))
      (node (ref "Q3") (pin "2") (pinfunction "S_2") (pintype "bidirectional"))
      (node (ref "R2") (pin "1") (pinfunction "1_1") (pintype "passive"))
    )
    (net (code "35") (name "Net-(Q2-D)") (class "Default")
      (node (ref "JP2") (pin "1") (pinfunction "1_1") (pintype "passive"))
      (node (ref "Q2") (pin "3") (pinfunction "D_3") (pintype "bidirectional"))
      (node (ref "VR1") (pin "B1") (pinfunction "B1_B1") (pintype "bidirectional"))
    )
    (net (code "36") (name "Net-(Q2-G)") (class "Default")
      (node (ref "Q2") (pin "1") (pinfunction "G_1") (pintype "bidirectional"))
      (node (ref "Q3") (pin "3") (pinfunction "D_3") (pintype "bidirectional"))
      (node (ref "R1") (pin "1") (pinfunction "1_1") (pintype "passive"))
    )
    (net (code "37") (name "Net-(Q4-D)") (class "Default")
      (node (ref "Q4") (pin "3") (pinfunction "D_3") (pintype "bidirectional"))
      (node (ref "Q5") (pin "1") (pinfunction "G_1") (pintype "bidirectional"))
      (node (ref "R3") (pin "1") (pinfunction "1_1") (pintype "passive"))
    )
    (net (code "38") (name "Net-(Q6-D)") (class "Default")
      (node (ref "JP3") (pin "1") (pinfunction "1_1") (pintype "passive"))
      (node (ref "Q6") (pin "3") (pinfunction "D_3") (pintype "bidirectional"))
      (node (ref "VR2") (pin "A1") (pinfunction "A1_A1") (pintype "bidirectional"))
    )
    (net (code "39") (name "Net-(Q6-G)") (class "Default")
      (node (ref "Q6") (pin "1") (pinfunction "G_1") (pintype "bidirectional"))
      (node (ref "Q7") (pin "3") (pinfunction "D_3") (pintype "bidirectional"))
      (node (ref "R4") (pin "1") (pinfunction "1_1") (pintype "passive"))
    )
    (net (code "40") (name "Net-(Q8-D)") (class "Default")
      (node (ref "Q8") (pin "3") (pinfunction "D_3") (pintype "bidirectional"))
      (node (ref "R7") (pin "1") (pinfunction "1_1") (pintype "passive"))
      (node (ref "R8") (pin "1") (pinfunction "1_1") (pintype "passive"))
    )
    (net (code "41") (name "Net-(Q8-G)") (class "Default")
      (node (ref "C1") (pin "1") (pinfunction "1_1") (pintype "passive"))
      (node (ref "Q8") (pin "1") (pinfunction "G_1") (pintype "bidirectional"))
      (node (ref "R5") (pin "2") (pinfunction "2_2") (pintype "passive"))
      (node (ref "R6") (pin "2") (pinfunction "2_2") (pintype "passive"))
    )
    (net (code "42") (name "Net-(R28-Pad1)") (class "Default")
      (node (ref "R28") (pin "1") (pinfunction "1_1") (pintype "passive"))
      (node (ref "R31") (pin "2") (pinfunction "2_2") (pintype "passive"))
    )
    (net (code "43") (name "Net-(R34-Pad1)") (class "Default")
      (node (ref "R34") (pin "1") (pinfunction "1_1") (pintype "passive"))
      (node (ref "R37") (pin "2") (pinfunction "2_2") (pintype "passive"))
    )
    (net (code "44") (name "PRE") (class "Default")
      (node (ref "AND4") (pin "2") (pinfunction "B_2") (pintype "input"))
      (node (ref "J3") (pin "3") (pinfunction "3_3") (pintype "bidirectional"))
    )
    (net (code "45") (name "RED") (class "Default")
      (node (ref "J4") (pin "3") (pinfunction "3_3") (pintype "bidirectional"))
      (node (ref "VR2") (pin "B1") (pinfunction "B1_B1") (pintype "bidirectional"))
    )
    (net (code "46") (name "TS_OFF_BAT") (class "Default")
      (node (ref "AND5") (pin "2") (pinfunction "B_2") (pintype "input"))
      (node (ref "IC3") (pin "3") (pinfunction "1IN+_3") (pintype "bidirectional"))
      (node (ref "IC3") (pin "6") (pinfunction "2IN-_6") (pintype "bidirectional"))
      (node (ref "J3") (pin "4") (pinfunction "4_4") (pintype "bidirectional"))
      (node (ref "Q4") (pin "2") (pinfunction "S_2") (pintype "bidirectional"))
      (node (ref "R26") (pin "1") (pinfunction "1_1") (pintype "passive"))
      (node (ref "R29") (pin "2") (pinfunction "2_2") (pintype "passive"))
      (node (ref "XOR1") (pin "1") (pinfunction "A_1") (pintype "bidirectional"))
    )
    (net (code "47") (name "TS_OFF_INV") (class "Default")
      (node (ref "IC5") (pin "3") (pinfunction "1IN+_3") (pintype "bidirectional"))
      (node (ref "IC5") (pin "6") (pinfunction "2IN-_6") (pintype "bidirectional"))
      (node (ref "J3") (pin "5") (pinfunction "5_5") (pintype "bidirectional"))
      (node (ref "R32") (pin "1") (pinfunction "1_1") (pintype "passive"))
      (node (ref "R35") (pin "2") (pinfunction "2_2") (pintype "passive"))
      (node (ref "XOR1") (pin "2") (pinfunction "B_2") (pintype "bidirectional"))
    )
    (net (code "48") (name "unconnected-(J3-Pad6)") (class "Default")
      (node (ref "J3") (pin "6") (pinfunction "6_6") (pintype "bidirectional"))
    )
    (net (code "49") (name "unconnected-(VR1-PadC1)") (class "Default")
      (node (ref "VR1") (pin "C1") (pinfunction "C1_C1") (pintype "bidirectional"))
    )
    (net (code "50") (name "unconnected-(VR2-PadC1)") (class "Default")
      (node (ref "VR2") (pin "C1") (pinfunction "C1_C1") (pintype "bidirectional"))
    )
  )
)
